# ee242a-lab4-amp_-values2.net
KiCad netlist of a schematic drawn in EAGLE
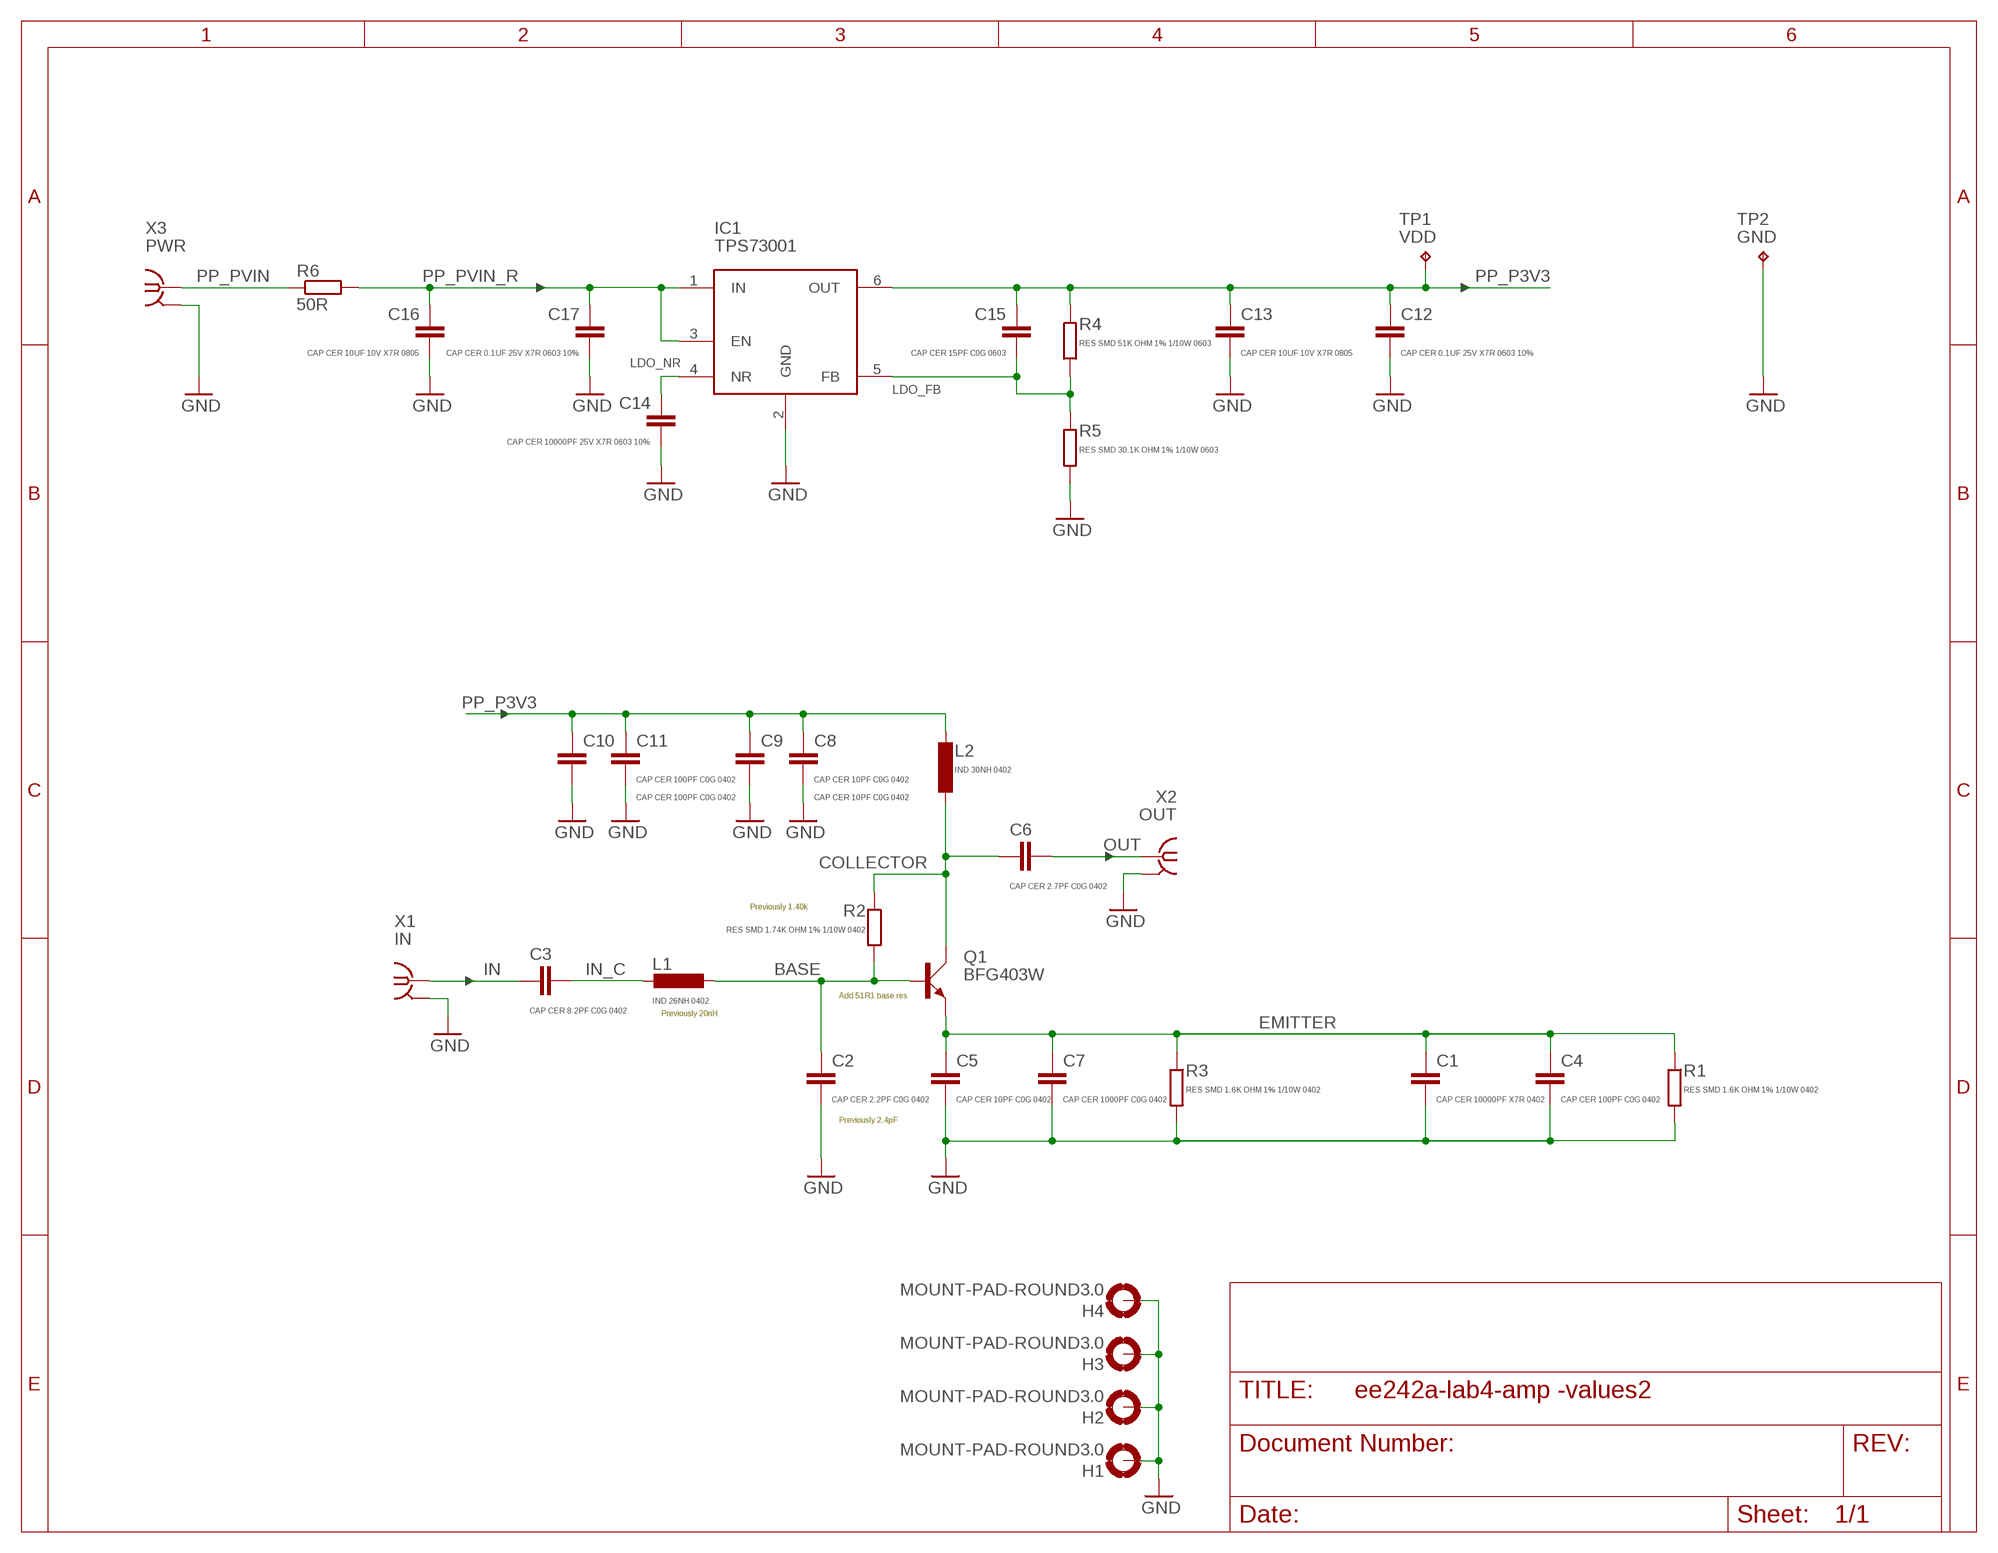
[diagram p0: schematic, sheet 1]

(export (version "E")
  (design (tool "Eeschema 10.0.6"))
  (components
    (comp (ref "C1")
      (value "CAP CER 10000PF X7R 0402")
      (footprint "eagle-import:C0402")
      (libsource (lib "eagle-import") (part "rcl-modified-footprints_C-EUC0402"))
    )
    (comp (ref "C2")
      (value "CAP CER 2.2PF C0G 0402")
      (footprint "eagle-import:C0402")
      (libsource (lib "eagle-import") (part "rcl-modified-footprints_C-EUC0402"))
    )
    (comp (ref "C3")
      (value "CAP CER 8.2PF C0G 0402")
      (footprint "eagle-import:C0402")
      (libsource (lib "eagle-import") (part "rcl-modified-footprints_C-EUC0402"))
    )
    (comp (ref "C4")
      (value "CAP CER 100PF C0G 0402")
      (footprint "eagle-import:C0402")
      (libsource (lib "eagle-import") (part "rcl-modified-footprints_C-EUC0402"))
    )
    (comp (ref "C5")
      (value "CAP CER 10PF C0G 0402")
      (footprint "eagle-import:C0402")
      (libsource (lib "eagle-import") (part "rcl-modified-footprints_C-EUC0402"))
    )
    (comp (ref "C6")
      (value "CAP CER 2.7PF C0G 0402")
      (footprint "eagle-import:C0402")
      (libsource (lib "eagle-import") (part "rcl-modified-footprints_C-EUC0402"))
    )
    (comp (ref "C7")
      (value "CAP CER 1000PF C0G 0402")
      (footprint "eagle-import:C0402")
      (libsource (lib "eagle-import") (part "rcl-modified-footprints_C-EUC0402"))
    )
    (comp (ref "C8")
      (value "CAP CER 10PF C0G 0402")
      (footprint "eagle-import:C0402")
      (libsource (lib "eagle-import") (part "rcl-modified-footprints_C-EUC0402"))
    )
    (comp (ref "C9")
      (value "CAP CER 10PF C0G 0402")
      (footprint "eagle-import:C0402")
      (libsource (lib "eagle-import") (part "rcl-modified-footprints_C-EUC0402"))
    )
    (comp (ref "C10")
      (value "CAP CER 100PF C0G 0402")
      (footprint "eagle-import:C0402")
      (libsource (lib "eagle-import") (part "rcl-modified-footprints_C-EUC0402"))
    )
    (comp (ref "C11")
      (value "CAP CER 100PF C0G 0402")
      (footprint "eagle-import:C0402")
      (libsource (lib "eagle-import") (part "rcl-modified-footprints_C-EUC0402"))
    )
    (comp (ref "C12")
      (value "CAP CER 0.1UF 25V X7R 0603 10%")
      (footprint "eagle-import:C0603")
      (libsource (lib "eagle-import") (part "rcl-modified-footprints_C-EUC0603"))
    )
    (comp (ref "C13")
      (value "CAP CER 10UF 10V X7R 0805")
      (footprint "eagle-import:C0805")
      (libsource (lib "eagle-import") (part "C-EUC0805"))
    )
    (comp (ref "C14")
      (value "CAP CER 10000PF 25V X7R 0603 10%")
      (footprint "eagle-import:C0603")
      (libsource (lib "eagle-import") (part "rcl-modified-footprints_C-EUC0603"))
    )
    (comp (ref "C15")
      (value "CAP CER 15PF C0G 0603")
      (footprint "eagle-import:C0603")
      (libsource (lib "eagle-import") (part "rcl-modified-footprints_C-EUC0603"))
    )
    (comp (ref "C16")
      (value "CAP CER 10UF 10V X7R 0805")
      (footprint "eagle-import:C0805")
      (libsource (lib "eagle-import") (part "C-EUC0805"))
    )
    (comp (ref "C17")
      (value "CAP CER 0.1UF 25V X7R 0603 10%")
      (footprint "eagle-import:C0603")
      (libsource (lib "eagle-import") (part "rcl-modified-footprints_C-EUC0603"))
    )
    (comp (ref "H1")
      (value "MOUNT-PAD-ROUND3.0")
      (footprint "eagle-import:3,0-PAD")
      (libsource (lib "eagle-import") (part "MOUNT-PAD-ROUND3.0"))
    )
    (comp (ref "H2")
      (value "MOUNT-PAD-ROUND3.0")
      (footprint "eagle-import:3,0-PAD")
      (libsource (lib "eagle-import") (part "MOUNT-PAD-ROUND3.0"))
    )
    (comp (ref "H3")
      (value "MOUNT-PAD-ROUND3.0")
      (footprint "eagle-import:3,0-PAD")
      (libsource (lib "eagle-import") (part "MOUNT-PAD-ROUND3.0"))
    )
    (comp (ref "H4")
      (value "MOUNT-PAD-ROUND3.0")
      (footprint "eagle-import:3,0-PAD")
      (libsource (lib "eagle-import") (part "MOUNT-PAD-ROUND3.0"))
    )
    (comp (ref "IC1")
      (value "TPS73001")
      (footprint "eagle-import:SOT23-6L")
      (libsource (lib "eagle-import") (part "TPS73001"))
    )
    (comp (ref "L1")
      (value "IND 26NH 0402")
      (footprint "eagle-import:R0402")
      (libsource (lib "eagle-import") (part "L-EU0402"))
    )
    (comp (ref "L2")
      (value "IND 30NH 0402")
      (footprint "eagle-import:R0402")
      (libsource (lib "eagle-import") (part "L-EU0402"))
    )
    (comp (ref "Q1")
      (value "BFG403W")
      (footprint "eagle-import:SOT343R")
      (libsource (lib "eagle-import") (part "BFG403W"))
    )
    (comp (ref "R1")
      (value "RES SMD 1.6K OHM 1% 1/10W 0402")
      (footprint "eagle-import:R0402")
      (libsource (lib "eagle-import") (part "R-EU_R0402"))
    )
    (comp (ref "R2")
      (value "RES SMD 1.74K OHM 1% 1/10W 0402")
      (footprint "eagle-import:R0402")
      (libsource (lib "eagle-import") (part "R-EU_R0402"))
    )
    (comp (ref "R3")
      (value "RES SMD 1.6K OHM 1% 1/10W 0402")
      (footprint "eagle-import:R0402")
      (libsource (lib "eagle-import") (part "R-EU_R0402"))
    )
    (comp (ref "R4")
      (value "RES SMD 51K OHM 1% 1/10W 0603")
      (footprint "eagle-import:R0603")
      (libsource (lib "eagle-import") (part "R-EU_R0603"))
    )
    (comp (ref "R5")
      (value "RES SMD 30.1K OHM 1% 1/10W 0603")
      (footprint "eagle-import:R0603")
      (libsource (lib "eagle-import") (part "R-EU_R0603"))
    )
    (comp (ref "R6")
      (value "50R")
      (footprint "eagle-import:R0805")
      (libsource (lib "eagle-import") (part "R-EU_R0805"))
    )
    (comp (ref "TP1")
      (value "VDD")
      (footprint "eagle-import:KEYSTONE_5000_MINIATURE")
      (libsource (lib "eagle-import") (part "KEYSTONE_5000"))
    )
    (comp (ref "TP2")
      (value "GND")
      (footprint "eagle-import:KEYSTONE_5000_MINIATURE")
      (libsource (lib "eagle-import") (part "KEYSTONE_5000"))
    )
    (comp (ref "X1")
      (value "IN")
      (footprint "eagle-import:J502-ND-142-0701-881_886")
      (fields (field (name "MF") "JOHNSON COMPONENTS") (field (name "MPN") "142-0701-881"))
      (libsource (lib "eagle-import") (part "SMA-142-0701-881/886"))
    )
    (comp (ref "X2")
      (value "OUT")
      (footprint "eagle-import:J502-ND-142-0701-881_886")
      (fields (field (name "MF") "JOHNSON COMPONENTS") (field (name "MPN") "142-0701-881"))
      (libsource (lib "eagle-import") (part "SMA-142-0701-881/886"))
    )
    (comp (ref "X3")
      (value "PWR")
      (footprint "eagle-import:J502-ND-142-0701-881_886")
      (fields (field (name "MF") "JOHNSON COMPONENTS") (field (name "MPN") "142-0701-881"))
      (libsource (lib "eagle-import") (part "SMA-142-0701-881/886"))
    )
  )
  (nets
    (net (code "1") (name "/BASE") (class "Default")
      (node (ref "C2") (pin "1") (pinfunction "1_1") (pintype "passive"))
      (node (ref "L1") (pin "2") (pinfunction "2_2") (pintype "passive"))
      (node (ref "Q1") (pin "2") (pinfunction "B_2") (pintype "passive"))
      (node (ref "R2") (pin "2") (pinfunction "2_2") (pintype "passive"))
    )
    (net (code "2") (name "/COLLECTOR") (class "Default")
      (node (ref "C6") (pin "1") (pinfunction "1_1") (pintype "passive"))
      (node (ref "L2") (pin "2") (pinfunction "2_2") (pintype "passive"))
      (node (ref "Q1") (pin "4") (pinfunction "C_4") (pintype "passive"))
      (node (ref "R2") (pin "1") (pinfunction "1_1") (pintype "passive"))
    )
    (net (code "3") (name "/EMITTER") (class "Default")
      (node (ref "C1") (pin "1") (pinfunction "1_1") (pintype "passive"))
      (node (ref "C4") (pin "1") (pinfunction "1_1") (pintype "passive"))
      (node (ref "C5") (pin "1") (pinfunction "1_1") (pintype "passive"))
      (node (ref "C7") (pin "1") (pinfunction "1_1") (pintype "passive"))
      (node (ref "Q1") (pin "1") (pinfunction "E_1") (pintype "passive"))
      (node (ref "Q1") (pin "3") (pinfunction "E_3") (pintype "passive"))
      (node (ref "R1") (pin "1") (pinfunction "1_1") (pintype "passive"))
      (node (ref "R3") (pin "1") (pinfunction "1_1") (pintype "passive"))
    )
    (net (code "4") (name "/IN") (class "Default")
      (node (ref "C3") (pin "1") (pinfunction "1_1") (pintype "passive"))
      (node (ref "X1") (pin "1") (pinfunction "1_1") (pintype "passive"))
    )
    (net (code "5") (name "/IN_C") (class "Default")
      (node (ref "C3") (pin "2") (pinfunction "2_2") (pintype "passive"))
      (node (ref "L1") (pin "1") (pinfunction "1_1") (pintype "passive"))
    )
    (net (code "6") (name "/LDO_FB") (class "Default")
      (node (ref "C15") (pin "2") (pinfunction "2_2") (pintype "passive"))
      (node (ref "IC1") (pin "5") (pinfunction "FB_5") (pintype "bidirectional"))
      (node (ref "R4") (pin "1") (pinfunction "1_1") (pintype "passive"))
      (node (ref "R5") (pin "1") (pinfunction "1_1") (pintype "passive"))
    )
    (net (code "7") (name "/LDO_NR") (class "Default")
      (node (ref "C14") (pin "1") (pinfunction "1_1") (pintype "passive"))
      (node (ref "IC1") (pin "4") (pinfunction "NR_4") (pintype "bidirectional"))
    )
    (net (code "8") (name "/OUT") (class "Default")
      (node (ref "C6") (pin "2") (pinfunction "2_2") (pintype "passive"))
      (node (ref "X2") (pin "1") (pinfunction "1_1") (pintype "passive"))
    )
    (net (code "9") (name "/PP_P3V3") (class "Default")
      (node (ref "C10") (pin "1") (pinfunction "1_1") (pintype "passive"))
      (node (ref "C11") (pin "1") (pinfunction "1_1") (pintype "passive"))
      (node (ref "C12") (pin "1") (pinfunction "1_1") (pintype "passive"))
      (node (ref "C13") (pin "1") (pinfunction "1_1") (pintype "passive"))
      (node (ref "C15") (pin "1") (pinfunction "1_1") (pintype "passive"))
      (node (ref "C8") (pin "1") (pinfunction "1_1") (pintype "passive"))
      (node (ref "C9") (pin "1") (pinfunction "1_1") (pintype "passive"))
      (node (ref "IC1") (pin "6") (pinfunction "OUT_6") (pintype "bidirectional"))
      (node (ref "L2") (pin "1") (pinfunction "1_1") (pintype "passive"))
      (node (ref "R4") (pin "2") (pinfunction "2_2") (pintype "passive"))
      (node (ref "TP1") (pin "P$1") (pinfunction "P$1_P$1") (pintype "bidirectional"))
    )
    (net (code "10") (name "/PP_PVIN") (class "Default")
      (node (ref "R6") (pin "1") (pinfunction "1_1") (pintype "passive"))
      (node (ref "X3") (pin "1") (pinfunction "1_1") (pintype "passive"))
    )
    (net (code "11") (name "/PP_PVIN_R") (class "Default")
      (node (ref "C16") (pin "1") (pinfunction "1_1") (pintype "passive"))
      (node (ref "C17") (pin "1") (pinfunction "1_1") (pintype "passive"))
      (node (ref "IC1") (pin "1") (pinfunction "IN_1") (pintype "bidirectional"))
      (node (ref "IC1") (pin "3") (pinfunction "EN_3") (pintype "bidirectional"))
      (node (ref "R6") (pin "2") (pinfunction "2_2") (pintype "passive"))
    )
    (net (code "12") (name "GND") (class "Default")
      (node (ref "C1") (pin "2") (pinfunction "2_2") (pintype "passive"))
      (node (ref "C10") (pin "2") (pinfunction "2_2") (pintype "passive"))
      (node (ref "C11") (pin "2") (pinfunction "2_2") (pintype "passive"))
      (node (ref "C12") (pin "2") (pinfunction "2_2") (pintype "passive"))
      (node (ref "C13") (pin "2") (pinfunction "2_2") (pintype "passive"))
      (node (ref "C14") (pin "2") (pinfunction "2_2") (pintype "passive"))
      (node (ref "C16") (pin "2") (pinfunction "2_2") (pintype "passive"))
      (node (ref "C17") (pin "2") (pinfunction "2_2") (pintype "passive"))
      (node (ref "C2") (pin "2") (pinfunction "2_2") (pintype "passive"))
      (node (ref "C4") (pin "2") (pinfunction "2_2") (pintype "passive"))
      (node (ref "C5") (pin "2") (pinfunction "2_2") (pintype "passive"))
      (node (ref "C7") (pin "2") (pinfunction "2_2") (pintype "passive"))
      (node (ref "C8") (pin "2") (pinfunction "2_2") (pintype "passive"))
      (node (ref "C9") (pin "2") (pinfunction "2_2") (pintype "passive"))
      (node (ref "H1") (pin "B3,0") (pinfunction "MOUNT_B3,0") (pintype "passive"))
      (node (ref "H2") (pin "B3,0") (pinfunction "MOUNT_B3,0") (pintype "passive"))
      (node (ref "H3") (pin "B3,0") (pinfunction "MOUNT_B3,0") (pintype "passive"))
      (node (ref "H4") (pin "B3,0") (pinfunction "MOUNT_B3,0") (pintype "passive"))
      (node (ref "IC1") (pin "2") (pinfunction "GND_2") (pintype "bidirectional"))
      (node (ref "R1") (pin "2") (pinfunction "2_2") (pintype "passive"))
      (node (ref "R3") (pin "2") (pinfunction "2_2") (pintype "passive"))
      (node (ref "R5") (pin "2") (pinfunction "2_2") (pintype "passive"))
      (node (ref "TP2") (pin "P$1") (pinfunction "P$1_P$1") (pintype "bidirectional"))
      (node (ref "X1") (pin "G@1") (pinfunction "GND_G@1") (pintype "power_in"))
      (node (ref "X2") (pin "G@1") (pinfunction "GND_G@1") (pintype "power_in"))
      (node (ref "X3") (pin "G@1") (pinfunction "GND_G@1") (pintype "power_in"))
    )
  )
)
